# multi-pcb-cruisecontrol.net
KiCad netlist of a schematic drawn in EAGLE
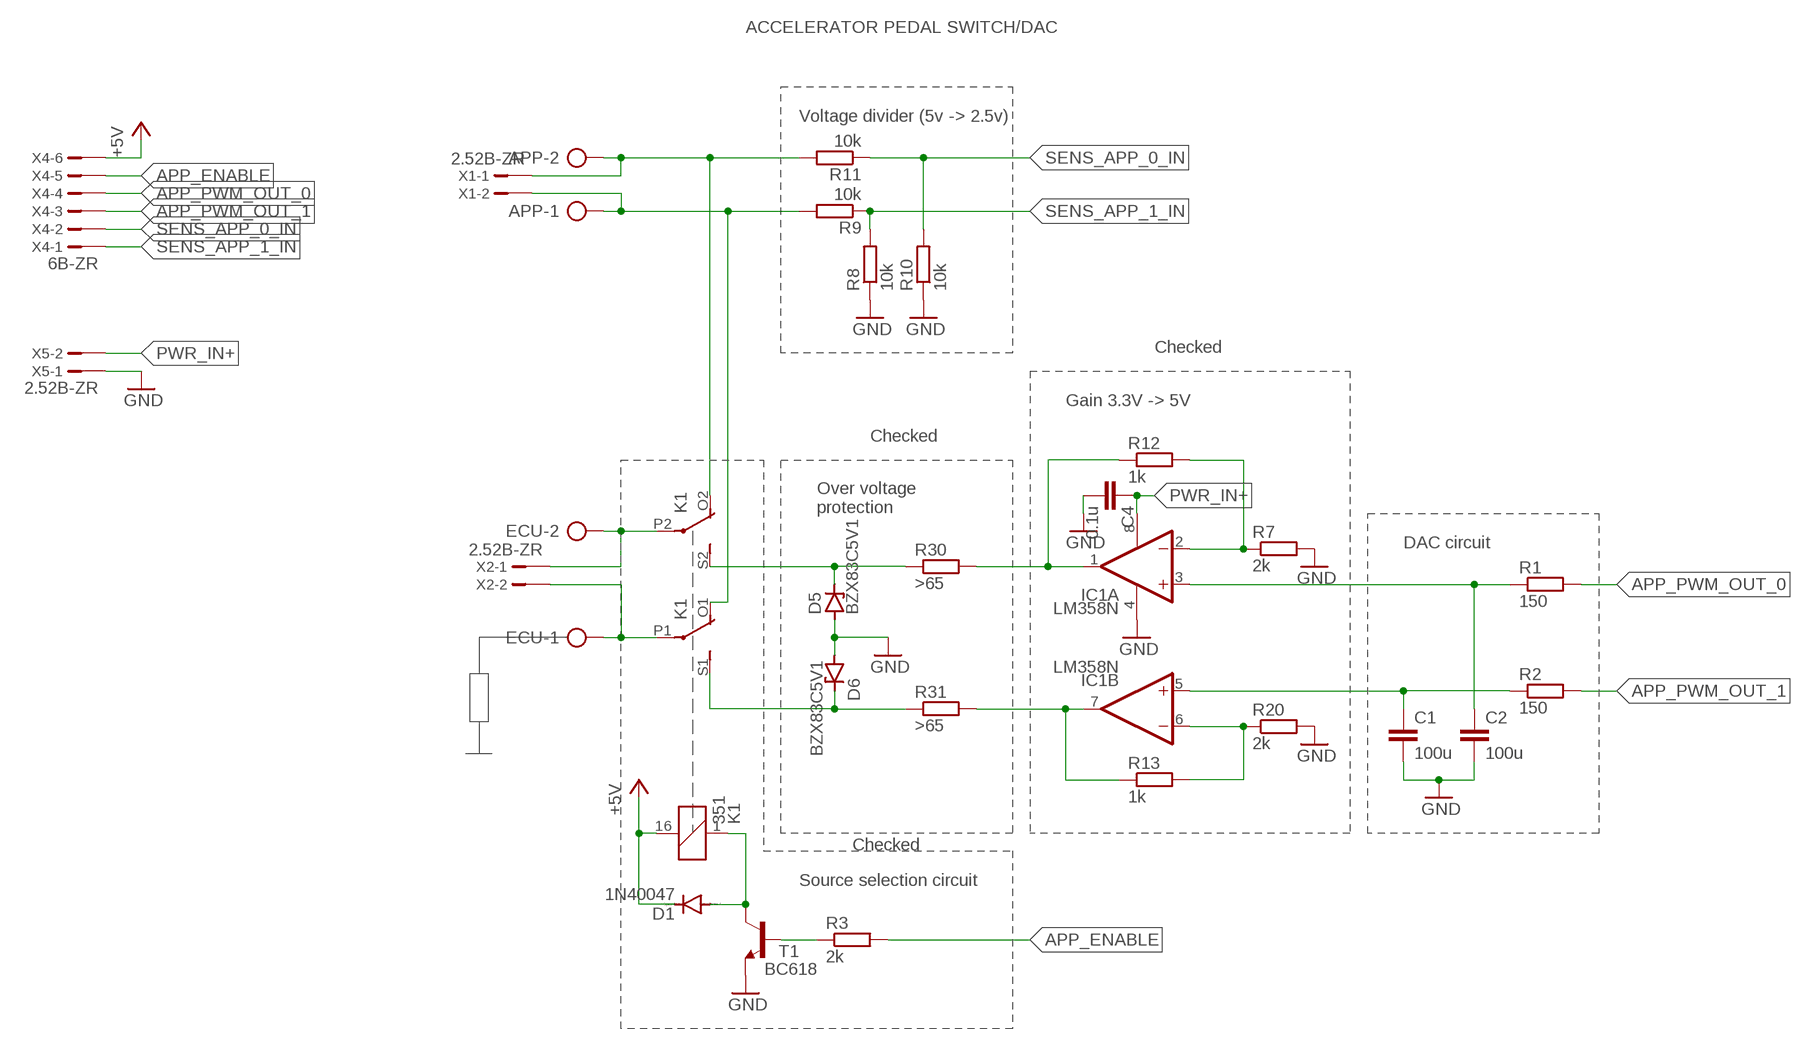
[diagram p0: schematic, sheet 1]

(export (version "E")
  (design (tool "Eeschema 10.0.6"))
  (components
    (comp (ref "APP")
      (value "AK300/2")
      (footprint "eagle-import:AK300_2")
      (libsource (lib "eagle-import") (part "AK300/2"))
    )
    (comp (ref "C1")
      (value "100u")
      (footprint "eagle-import:C025-050X050")
      (libsource (lib "eagle-import") (part "C-EU025-050X050"))
    )
    (comp (ref "C2")
      (value "100u")
      (footprint "eagle-import:C025-050X050")
      (libsource (lib "eagle-import") (part "C-EU025-050X050"))
    )
    (comp (ref "C4")
      (value "0.1u")
      (footprint "eagle-import:C025-050X050")
      (libsource (lib "eagle-import") (part "C-EU025-050X050"))
    )
    (comp (ref "D1")
      (value "1N40047")
      (footprint "eagle-import:DO41-7.6")
      (libsource (lib "eagle-import") (part "1N40047"))
    )
    (comp (ref "D5")
      (value "BZX83C5V1")
      (footprint "eagle-import:DO41Z7.6")
      (libsource (lib "eagle-import") (part "BZX857"))
    )
    (comp (ref "D6")
      (value "BZX83C5V1")
      (footprint "eagle-import:DO41Z7.6")
      (libsource (lib "eagle-import") (part "BZX857"))
    )
    (comp (ref "ECU")
      (value "AK300/2")
      (footprint "eagle-import:AK300_2")
      (libsource (lib "eagle-import") (part "AK300/2"))
    )
    (comp (ref "IC1")
      (value "LM358N")
      (footprint "eagle-import:DIL08")
      (libsource (lib "eagle-import") (part "LM358N"))
    )
    (comp (ref "K1")
      (value "351")
      (footprint "eagle-import:351")
      (libsource (lib "eagle-import") (part "351"))
    )
    (comp (ref "R1")
      (value "150")
      (footprint "eagle-import:0207_7")
      (libsource (lib "eagle-import") (part "R-EU_0207/7"))
    )
    (comp (ref "R2")
      (value "150")
      (footprint "eagle-import:0207_7")
      (libsource (lib "eagle-import") (part "R-EU_0207/7"))
    )
    (comp (ref "R3")
      (value "2k")
      (footprint "eagle-import:0207_7")
      (libsource (lib "eagle-import") (part "R-EU_0207/7"))
    )
    (comp (ref "R7")
      (value "2k")
      (footprint "eagle-import:0207_7")
      (libsource (lib "eagle-import") (part "R-EU_0207/7"))
    )
    (comp (ref "R8")
      (value "10k")
      (footprint "eagle-import:0207_7")
      (libsource (lib "eagle-import") (part "R-EU_0207/7"))
    )
    (comp (ref "R9")
      (value "10k")
      (footprint "eagle-import:0207_7")
      (libsource (lib "eagle-import") (part "R-EU_0207/7"))
    )
    (comp (ref "R10")
      (value "10k")
      (footprint "eagle-import:0207_7")
      (libsource (lib "eagle-import") (part "R-EU_0207/7"))
    )
    (comp (ref "R11")
      (value "10k")
      (footprint "eagle-import:0207_7")
      (libsource (lib "eagle-import") (part "R-EU_0207/7"))
    )
    (comp (ref "R12")
      (value "1k")
      (footprint "eagle-import:0207_7")
      (libsource (lib "eagle-import") (part "R-EU_0207/7"))
    )
    (comp (ref "R13")
      (value "1k")
      (footprint "eagle-import:0207_7")
      (libsource (lib "eagle-import") (part "R-EU_0207/7"))
    )
    (comp (ref "R20")
      (value "2k")
      (footprint "eagle-import:0207_7")
      (libsource (lib "eagle-import") (part "R-EU_0207/7"))
    )
    (comp (ref "R30")
      (value ">65")
      (footprint "eagle-import:0207_7")
      (libsource (lib "eagle-import") (part "R-EU_0207/7"))
    )
    (comp (ref "R31")
      (value ">65")
      (footprint "eagle-import:0207_7")
      (libsource (lib "eagle-import") (part "R-EU_0207/7"))
    )
    (comp (ref "T1")
      (value "BC618")
      (footprint "eagle-import:TO92-EBC")
      (libsource (lib "eagle-import") (part "BC618"))
    )
    (comp (ref "X1")
      (value "2.52B-ZR")
      (footprint "eagle-import:B2B-ZR2.5")
      (libsource (lib "eagle-import") (part "?2B-ZR2.5"))
    )
    (comp (ref "X2")
      (value "2.52B-ZR")
      (footprint "eagle-import:B2B-ZR2.5")
      (libsource (lib "eagle-import") (part "?2B-ZR2.5"))
    )
    (comp (ref "X4")
      (value "6B-ZR")
      (footprint "eagle-import:B6B-ZR2.5")
      (libsource (lib "eagle-import") (part "?6B-ZR"))
    )
    (comp (ref "X5")
      (value "2.52B-ZR")
      (footprint "eagle-import:B2B-ZR2.5")
      (libsource (lib "eagle-import") (part "?2B-ZR2.5"))
    )
  )
  (nets
    (net (code "1") (name "+5V") (class "Default")
      (node (ref "D1") (pin "C") (pinfunction "C_C") (pintype "passive"))
      (node (ref "K1") (pin "16") (pinfunction "2_16") (pintype "passive"))
      (node (ref "X4") (pin "6") (pinfunction "1_6") (pintype "passive"))
    )
    (net (code "2") (name "APP_ENABLE") (class "Default")
      (node (ref "R3") (pin "2") (pinfunction "2_2") (pintype "passive"))
      (node (ref "X4") (pin "5") (pinfunction "1_5") (pintype "passive"))
    )
    (net (code "3") (name "APP_PWM_OUT_0") (class "Default")
      (node (ref "R1") (pin "2") (pinfunction "2_2") (pintype "passive"))
      (node (ref "X4") (pin "4") (pinfunction "1_4") (pintype "passive"))
    )
    (net (code "4") (name "APP_PWM_OUT_1") (class "Default")
      (node (ref "R2") (pin "2") (pinfunction "2_2") (pintype "passive"))
      (node (ref "X4") (pin "3") (pinfunction "1_3") (pintype "passive"))
    )
    (net (code "5") (name "GND") (class "Default")
      (node (ref "C1") (pin "2") (pinfunction "2_2") (pintype "passive"))
      (node (ref "C2") (pin "2") (pinfunction "2_2") (pintype "passive"))
      (node (ref "C4") (pin "2") (pinfunction "2_2") (pintype "passive"))
      (node (ref "D5") (pin "A") (pinfunction "A_A") (pintype "passive"))
      (node (ref "D6") (pin "A") (pinfunction "A_A") (pintype "passive"))
      (node (ref "IC1") (pin "4") (pinfunction "V-_4") (pintype "power_in"))
      (node (ref "R10") (pin "1") (pinfunction "1_1") (pintype "passive"))
      (node (ref "R20") (pin "2") (pinfunction "2_2") (pintype "passive"))
      (node (ref "R7") (pin "2") (pinfunction "2_2") (pintype "passive"))
      (node (ref "R8") (pin "1") (pinfunction "1_1") (pintype "passive"))
      (node (ref "T1") (pin "E") (pinfunction "E_E") (pintype "passive"))
      (node (ref "X5") (pin "1") (pinfunction "1_1") (pintype "passive"))
    )
    (net (code "6") (name "Net-(APPA-KL)") (class "Default")
      (node (ref "APP") (pin "1") (pinfunction "KL_1") (pintype "passive"))
      (node (ref "K1") (pin "O1") (pinfunction "O_O1") (pintype "passive"))
      (node (ref "R9") (pin "2") (pinfunction "2_2") (pintype "passive"))
      (node (ref "X1") (pin "2") (pinfunction "1_2") (pintype "passive"))
    )
    (net (code "7") (name "Net-(APPB-KL)") (class "Default")
      (node (ref "APP") (pin "2") (pinfunction "KL_2") (pintype "passive"))
      (node (ref "K1") (pin "O2") (pinfunction "O_O2") (pintype "passive"))
      (node (ref "R11") (pin "2") (pinfunction "2_2") (pintype "passive"))
      (node (ref "X1") (pin "1") (pinfunction "1_1") (pintype "passive"))
    )
    (net (code "8") (name "Net-(D1-PadA)") (class "Default")
      (node (ref "D1") (pin "A") (pinfunction "A_A") (pintype "passive"))
      (node (ref "K1") (pin "1") (pinfunction "1_1") (pintype "passive"))
      (node (ref "T1") (pin "C") (pinfunction "C_C") (pintype "passive"))
    )
    (net (code "9") (name "Net-(ECUA-KL)") (class "Default")
      (node (ref "ECU") (pin "1") (pinfunction "KL_1") (pintype "passive"))
      (node (ref "K1") (pin "P1") (pinfunction "P_P1") (pintype "passive"))
      (node (ref "X2") (pin "2") (pinfunction "1_2") (pintype "passive"))
    )
    (net (code "10") (name "Net-(ECUB-KL)") (class "Default")
      (node (ref "ECU") (pin "2") (pinfunction "KL_2") (pintype "passive"))
      (node (ref "K1") (pin "P2") (pinfunction "P_P2") (pintype "passive"))
      (node (ref "X2") (pin "1") (pinfunction "1_1") (pintype "passive"))
    )
    (net (code "11") (name "Net-(IC1A-+IN)") (class "Default")
      (node (ref "C2") (pin "1") (pinfunction "1_1") (pintype "passive"))
      (node (ref "IC1") (pin "3") (pinfunction "+IN_3") (pintype "input"))
      (node (ref "R1") (pin "1") (pinfunction "1_1") (pintype "passive"))
    )
    (net (code "12") (name "Net-(IC1A--IN)") (class "Default")
      (node (ref "IC1") (pin "2") (pinfunction "-IN_2") (pintype "input"))
      (node (ref "R12") (pin "2") (pinfunction "2_2") (pintype "passive"))
      (node (ref "R7") (pin "1") (pinfunction "1_1") (pintype "passive"))
    )
    (net (code "13") (name "Net-(IC1A-OUT)") (class "Default")
      (node (ref "IC1") (pin "1") (pinfunction "OUT_1") (pintype "output"))
      (node (ref "R12") (pin "1") (pinfunction "1_1") (pintype "passive"))
      (node (ref "R30") (pin "2") (pinfunction "2_2") (pintype "passive"))
    )
    (net (code "14") (name "Net-(IC1B-+IN)") (class "Default")
      (node (ref "C1") (pin "1") (pinfunction "1_1") (pintype "passive"))
      (node (ref "IC1") (pin "5") (pinfunction "+IN_5") (pintype "input"))
      (node (ref "R2") (pin "1") (pinfunction "1_1") (pintype "passive"))
    )
    (net (code "15") (name "Net-(IC1B--IN)") (class "Default")
      (node (ref "IC1") (pin "6") (pinfunction "-IN_6") (pintype "input"))
      (node (ref "R13") (pin "2") (pinfunction "2_2") (pintype "passive"))
      (node (ref "R20") (pin "1") (pinfunction "1_1") (pintype "passive"))
    )
    (net (code "16") (name "Net-(IC1B-OUT)") (class "Default")
      (node (ref "IC1") (pin "7") (pinfunction "OUT_7") (pintype "output"))
      (node (ref "R13") (pin "1") (pinfunction "1_1") (pintype "passive"))
      (node (ref "R31") (pin "2") (pinfunction "2_2") (pintype "passive"))
    )
    (net (code "17") (name "Net-(K1B-S)") (class "Default")
      (node (ref "D6") (pin "C") (pinfunction "C_C") (pintype "passive"))
      (node (ref "K1") (pin "S1") (pinfunction "S_S1") (pintype "passive"))
      (node (ref "R31") (pin "1") (pinfunction "1_1") (pintype "passive"))
    )
    (net (code "18") (name "Net-(K1C-S)") (class "Default")
      (node (ref "D5") (pin "C") (pinfunction "C_C") (pintype "passive"))
      (node (ref "K1") (pin "S2") (pinfunction "S_S2") (pintype "passive"))
      (node (ref "R30") (pin "1") (pinfunction "1_1") (pintype "passive"))
    )
    (net (code "19") (name "Net-(R3-Pad1)") (class "Default")
      (node (ref "R3") (pin "1") (pinfunction "1_1") (pintype "passive"))
      (node (ref "T1") (pin "B") (pinfunction "B_B") (pintype "passive"))
    )
    (net (code "20") (name "PWR_IN+") (class "Default")
      (node (ref "C4") (pin "1") (pinfunction "1_1") (pintype "passive"))
      (node (ref "IC1") (pin "8") (pinfunction "V+_8") (pintype "power_in"))
      (node (ref "X5") (pin "2") (pinfunction "1_2") (pintype "passive"))
    )
    (net (code "21") (name "SENS_APP_0_IN") (class "Default")
      (node (ref "R10") (pin "2") (pinfunction "2_2") (pintype "passive"))
      (node (ref "R11") (pin "1") (pinfunction "1_1") (pintype "passive"))
      (node (ref "X4") (pin "2") (pinfunction "1_2") (pintype "passive"))
    )
    (net (code "22") (name "SENS_APP_1_IN") (class "Default")
      (node (ref "R8") (pin "2") (pinfunction "2_2") (pintype "passive"))
      (node (ref "R9") (pin "1") (pinfunction "1_1") (pintype "passive"))
      (node (ref "X4") (pin "1") (pinfunction "1_1") (pintype "passive"))
    )
  )
)
